# MB.net
KiCad netlist of a schematic drawn in EAGLE
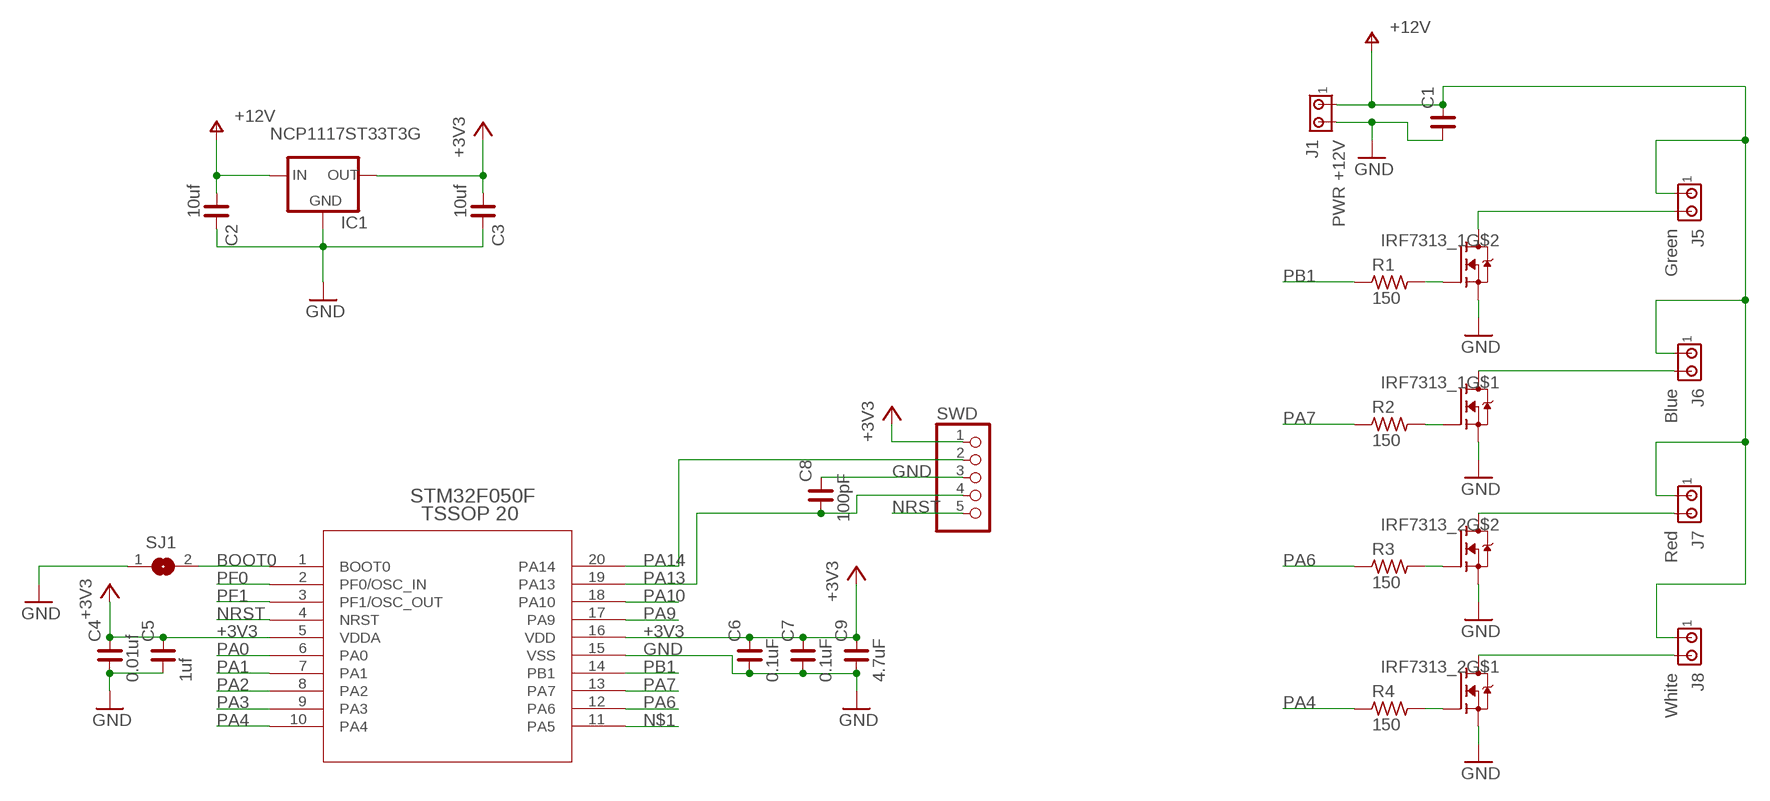
[diagram p0: schematic, sheet 1]

(export (version "E")
  (design (tool "Eeschema 10.0.6"))
  (components
    (comp (ref "C1")
      (value "C_1206")
      (footprint "eagle-import:C1206")
      (libsource (lib "eagle-import") (part "C_1206"))
    )
    (comp (ref "C2")
      (value "10uf")
      (footprint "eagle-import:C1206")
      (libsource (lib "eagle-import") (part "C_1206"))
    )
    (comp (ref "C3")
      (value "10uf")
      (footprint "eagle-import:C1206")
      (libsource (lib "eagle-import") (part "C_1206"))
    )
    (comp (ref "C4")
      (value "0.01uf")
      (footprint "eagle-import:C1206")
      (libsource (lib "eagle-import") (part "C_1206"))
    )
    (comp (ref "C5")
      (value "1uf")
      (footprint "eagle-import:C1206")
      (libsource (lib "eagle-import") (part "C_1206"))
    )
    (comp (ref "C6")
      (value "0.1uF")
      (footprint "eagle-import:C1206")
      (libsource (lib "eagle-import") (part "C_1206"))
    )
    (comp (ref "C7")
      (value "0.1uF")
      (footprint "eagle-import:C1206")
      (libsource (lib "eagle-import") (part "C_1206"))
    )
    (comp (ref "C8")
      (value "100pF")
      (footprint "eagle-import:C1206")
      (libsource (lib "eagle-import") (part "C_1206"))
    )
    (comp (ref "C9")
      (value "4.7uF")
      (footprint "eagle-import:C1206")
      (libsource (lib "eagle-import") (part "C_1206"))
    )
    (comp (ref "IC1")
      (value "NCP1117ST33T3G")
      (footprint "eagle-import:SOT223")
      (libsource (lib "eagle-import") (part "LM1117"))
    )
    (comp (ref "IRF7313_1")
      (value "IRF7313")
      (footprint "eagle-import:SO-8")
      (libsource (lib "eagle-import") (part "IRF7313"))
    )
    (comp (ref "IRF7313_2")
      (value "IRF7313")
      (footprint "eagle-import:SO-8")
      (libsource (lib "eagle-import") (part "IRF7313"))
    )
    (comp (ref "J1")
      (value "PWR +12V")
      (footprint "eagle-import:10X02MTA")
      (libsource (lib "eagle-import") (part "MTA02-100"))
    )
    (comp (ref "J5")
      (value "Green")
      (footprint "eagle-import:10X02MTA")
      (libsource (lib "eagle-import") (part "MTA02-100"))
    )
    (comp (ref "J6")
      (value "Blue")
      (footprint "eagle-import:10X02MTA")
      (libsource (lib "eagle-import") (part "MTA02-100"))
    )
    (comp (ref "J7")
      (value "Red")
      (footprint "eagle-import:10X02MTA")
      (libsource (lib "eagle-import") (part "MTA02-100"))
    )
    (comp (ref "J8")
      (value "White")
      (footprint "eagle-import:10X02MTA")
      (libsource (lib "eagle-import") (part "MTA02-100"))
    )
    (comp (ref "R1")
      (value "150")
      (footprint "eagle-import:R1206")
      (libsource (lib "eagle-import") (part "R_1206"))
    )
    (comp (ref "R2")
      (value "150")
      (footprint "eagle-import:R1206")
      (libsource (lib "eagle-import") (part "R_1206"))
    )
    (comp (ref "R3")
      (value "150")
      (footprint "eagle-import:R1206")
      (libsource (lib "eagle-import") (part "R_1206"))
    )
    (comp (ref "R4")
      (value "150")
      (footprint "eagle-import:R1206")
      (libsource (lib "eagle-import") (part "R_1206"))
    )
    (comp (ref "SJ1") (value "SJ") (footprint "eagle-import:SJ") (libsource (lib "eagle-import") (part "SJ")))
    (comp (ref "SWD")
      (value "PINHD-1X05_2.54-90°-S")
      (footprint "eagle-import:1X05_90-S")
      (libsource (lib "eagle-import") (part "PINHD-1X05_2.54-90°-S"))
    )
    (comp (ref "U$4")
      (value "STM32F050F4P6")
      (footprint "eagle-import:TSSOP20")
      (libsource (lib "eagle-import") (part "STM32F050F4P6"))
    )
  )
  (nets
    (net (code "1") (name "+3V3") (class "Default")
      (node (ref "C3") (pin "1") (pinfunction "1_1") (pintype "passive"))
      (node (ref "C4") (pin "2") (pinfunction "2_2") (pintype "passive"))
      (node (ref "C5") (pin "2") (pinfunction "2_2") (pintype "passive"))
      (node (ref "C6") (pin "2") (pinfunction "2_2") (pintype "passive"))
      (node (ref "C7") (pin "2") (pinfunction "2_2") (pintype "passive"))
      (node (ref "C9") (pin "2") (pinfunction "2_2") (pintype "passive"))
      (node (ref "IC1") (pin "2") (pinfunction "OUT_2") (pintype "passive"))
      (node (ref "SWD") (pin "1") (pinfunction "1_1") (pintype "passive"))
      (node (ref "U$4") (pin "16") (pinfunction "VDD_16") (pintype "passive"))
      (node (ref "U$4") (pin "5") (pinfunction "VDDA_5") (pintype "passive"))
    )
    (net (code "2") (name "/BOOT0") (class "Default")
      (node (ref "SJ1") (pin "2") (pinfunction "2_2") (pintype "passive"))
      (node (ref "U$4") (pin "1") (pinfunction "BOOT0_1") (pintype "passive"))
    )
    (net (code "3") (name "/N$1") (class "Default")
      (node (ref "U$4") (pin "11") (pinfunction "PA5_11") (pintype "passive"))
    )
    (net (code "4") (name "/NRST") (class "Default")
      (node (ref "SWD") (pin "5") (pinfunction "5_5") (pintype "passive"))
      (node (ref "U$4") (pin "4") (pinfunction "NRST_4") (pintype "passive"))
    )
    (net (code "5") (name "/PA0") (class "Default")
      (node (ref "U$4") (pin "6") (pinfunction "PA0_6") (pintype "passive"))
    )
    (net (code "6") (name "/PA1") (class "Default")
      (node (ref "U$4") (pin "7") (pinfunction "PA1_7") (pintype "passive"))
    )
    (net (code "7") (name "/PA2") (class "Default")
      (node (ref "U$4") (pin "8") (pinfunction "PA2_8") (pintype "passive"))
    )
    (net (code "8") (name "/PA3") (class "Default")
      (node (ref "U$4") (pin "9") (pinfunction "PA3_9") (pintype "passive"))
    )
    (net (code "9") (name "/PA4") (class "Default")
      (node (ref "R4") (pin "1") (pinfunction "1_1") (pintype "passive"))
      (node (ref "U$4") (pin "10") (pinfunction "PA4_10") (pintype "passive"))
    )
    (net (code "10") (name "/PA6") (class "Default")
      (node (ref "R3") (pin "1") (pinfunction "1_1") (pintype "passive"))
      (node (ref "U$4") (pin "12") (pinfunction "PA6_12") (pintype "passive"))
    )
    (net (code "11") (name "/PA7") (class "Default")
      (node (ref "R2") (pin "1") (pinfunction "1_1") (pintype "passive"))
      (node (ref "U$4") (pin "13") (pinfunction "PA7_13") (pintype "passive"))
    )
    (net (code "12") (name "/PA9") (class "Default")
      (node (ref "U$4") (pin "17") (pinfunction "PA9_17") (pintype "passive"))
    )
    (net (code "13") (name "/PA10") (class "Default")
      (node (ref "U$4") (pin "18") (pinfunction "PA10_18") (pintype "passive"))
    )
    (net (code "14") (name "/PA13") (class "Default")
      (node (ref "C8") (pin "1") (pinfunction "1_1") (pintype "passive"))
      (node (ref "SWD") (pin "4") (pinfunction "4_4") (pintype "passive"))
      (node (ref "U$4") (pin "19") (pinfunction "PA13_19") (pintype "passive"))
    )
    (net (code "15") (name "/PA14") (class "Default")
      (node (ref "SWD") (pin "2") (pinfunction "2_2") (pintype "passive"))
      (node (ref "U$4") (pin "20") (pinfunction "PA14_20") (pintype "passive"))
    )
    (net (code "16") (name "/PB1") (class "Default")
      (node (ref "R1") (pin "1") (pinfunction "1_1") (pintype "passive"))
      (node (ref "U$4") (pin "14") (pinfunction "PB1_14") (pintype "passive"))
    )
    (net (code "17") (name "/PF0") (class "Default")
      (node (ref "U$4") (pin "2") (pinfunction "PF0/OSC_IN_2") (pintype "passive"))
    )
    (net (code "18") (name "/PF1") (class "Default")
      (node (ref "U$4") (pin "3") (pinfunction "PF1/OSC_OUT_3") (pintype "passive"))
    )
    (net (code "19") (name "GND") (class "Default")
      (node (ref "C1") (pin "1") (pinfunction "1_1") (pintype "passive"))
      (node (ref "C2") (pin "2") (pinfunction "2_2") (pintype "passive"))
      (node (ref "C3") (pin "2") (pinfunction "2_2") (pintype "passive"))
      (node (ref "C4") (pin "1") (pinfunction "1_1") (pintype "passive"))
      (node (ref "C5") (pin "1") (pinfunction "1_1") (pintype "passive"))
      (node (ref "C6") (pin "1") (pinfunction "1_1") (pintype "passive"))
      (node (ref "C7") (pin "1") (pinfunction "1_1") (pintype "passive"))
      (node (ref "C8") (pin "2") (pinfunction "2_2") (pintype "passive"))
      (node (ref "C9") (pin "1") (pinfunction "1_1") (pintype "passive"))
      (node (ref "IC1") (pin "1") (pinfunction "GND_1") (pintype "input"))
      (node (ref "IRF7313_1") (pin "1") (pinfunction "S_1") (pintype "passive"))
      (node (ref "IRF7313_1") (pin "3") (pinfunction "S_3") (pintype "passive"))
      (node (ref "IRF7313_2") (pin "1") (pinfunction "S_1") (pintype "passive"))
      (node (ref "IRF7313_2") (pin "3") (pinfunction "S_3") (pintype "passive"))
      (node (ref "J1") (pin "2") (pinfunction "2_2") (pintype "passive"))
      (node (ref "SJ1") (pin "1") (pinfunction "1_1") (pintype "passive"))
      (node (ref "SWD") (pin "3") (pinfunction "3_3") (pintype "passive"))
      (node (ref "U$4") (pin "15") (pinfunction "VSS_15") (pintype "passive"))
    )
    (net (code "20") (name "Net-(IRF7313_1A-D-Pad7)") (class "Default")
      (node (ref "IRF7313_1") (pin "7") (pinfunction "D_7") (pintype "passive"))
      (node (ref "IRF7313_1") (pin "8") (pinfunction "D_8") (pintype "passive"))
      (node (ref "J6") (pin "2") (pinfunction "2_2") (pintype "passive"))
    )
    (net (code "21") (name "Net-(IRF7313_1A-G)") (class "Default")
      (node (ref "IRF7313_1") (pin "2") (pinfunction "G_2") (pintype "passive"))
      (node (ref "R2") (pin "2") (pinfunction "2_2") (pintype "passive"))
    )
    (net (code "22") (name "Net-(IRF7313_1B-D-Pad5)") (class "Default")
      (node (ref "IRF7313_1") (pin "5") (pinfunction "D_5") (pintype "passive"))
      (node (ref "IRF7313_1") (pin "6") (pinfunction "D_6") (pintype "passive"))
      (node (ref "J5") (pin "2") (pinfunction "2_2") (pintype "passive"))
    )
    (net (code "23") (name "Net-(IRF7313_1B-G)") (class "Default")
      (node (ref "IRF7313_1") (pin "4") (pinfunction "G_4") (pintype "passive"))
      (node (ref "R1") (pin "2") (pinfunction "2_2") (pintype "passive"))
    )
    (net (code "24") (name "Net-(IRF7313_2A-D-Pad7)") (class "Default")
      (node (ref "IRF7313_2") (pin "7") (pinfunction "D_7") (pintype "passive"))
      (node (ref "IRF7313_2") (pin "8") (pinfunction "D_8") (pintype "passive"))
      (node (ref "J8") (pin "2") (pinfunction "2_2") (pintype "passive"))
    )
    (net (code "25") (name "Net-(IRF7313_2A-G)") (class "Default")
      (node (ref "IRF7313_2") (pin "2") (pinfunction "G_2") (pintype "passive"))
      (node (ref "R4") (pin "2") (pinfunction "2_2") (pintype "passive"))
    )
    (net (code "26") (name "Net-(IRF7313_2B-D-Pad5)") (class "Default")
      (node (ref "IRF7313_2") (pin "5") (pinfunction "D_5") (pintype "passive"))
      (node (ref "IRF7313_2") (pin "6") (pinfunction "D_6") (pintype "passive"))
      (node (ref "J7") (pin "2") (pinfunction "2_2") (pintype "passive"))
    )
    (net (code "27") (name "Net-(IRF7313_2B-G)") (class "Default")
      (node (ref "IRF7313_2") (pin "4") (pinfunction "G_4") (pintype "passive"))
      (node (ref "R3") (pin "2") (pinfunction "2_2") (pintype "passive"))
    )
    (net (code "28") (name "V+") (class "Default")
      (node (ref "C1") (pin "2") (pinfunction "2_2") (pintype "passive"))
      (node (ref "C2") (pin "1") (pinfunction "1_1") (pintype "passive"))
      (node (ref "IC1") (pin "3") (pinfunction "IN_3") (pintype "input"))
      (node (ref "J1") (pin "1") (pinfunction "1_1") (pintype "passive"))
      (node (ref "J5") (pin "1") (pinfunction "1_1") (pintype "passive"))
      (node (ref "J6") (pin "1") (pinfunction "1_1") (pintype "passive"))
      (node (ref "J7") (pin "1") (pinfunction "1_1") (pintype "passive"))
      (node (ref "J8") (pin "1") (pinfunction "1_1") (pintype "passive"))
    )
  )
)
